# vlc_ctrl.net
KiCad netlist of a schematic drawn in Altium Designer
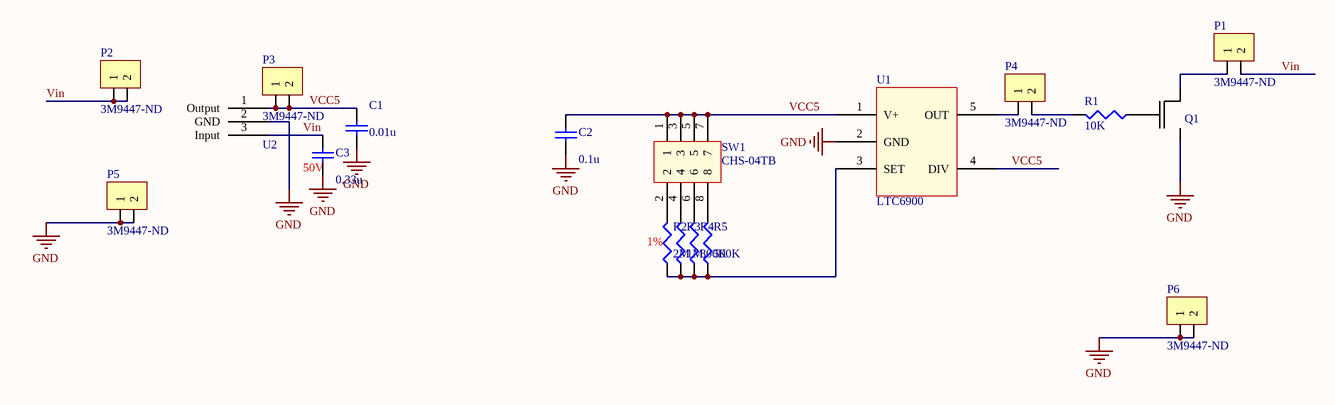
[diagram p0: vlc_ctrl.SchDoc]

(export (version "E")
  (design (tool "Eeschema 10.0.6"))
  (components
    (comp (ref "C1")
      (value "0.01u")
      (footprint "1608[0603]")
      (description "Capacitor (Semiconductor SIM Model)")
      (fields (field (name "Comment") "Cap Semi") (field (name "PUBLISHER") "Altium Limited"))
      (libsource (lib "Miscellaneous Devices") (part "Cap Semi"))
    )
    (comp (ref "C2")
      (value "0.1u")
      (footprint "1608[0603]")
      (description "Capacitor (Semiconductor SIM Model)")
      (fields (field (name "Comment") "Cap Semi") (field (name "PUBLISHER") "Altium Limited"))
      (libsource (lib "Miscellaneous Devices") (part "Cap Semi"))
    )
    (comp (ref "C3")
      (value "0.33u")
      (footprint "1608[0603]")
      (description "Capacitor (Semiconductor SIM Model)")
      (fields (field (name "Comment") "Cap Semi") (field (name "PUBLISHER") "Altium Limited"))
      (libsource (lib "Miscellaneous Devices") (part "Cap Semi"))
    )
    (comp (ref "P1")
      (value "1 x 2 header")
      (footprint "1x2 header")
      (description "100 mils standard header")
      (fields (field (name "SUPPLIER PART NUMBER 1") "3M9447-ND"))
      (libsource (lib "vlc_ctrl") (part "1 x 2 header"))
    )
    (comp (ref "P2")
      (value "1 x 2 header")
      (footprint "1x2 header")
      (description "100 mils standard header")
      (fields (field (name "SUPPLIER PART NUMBER 1") "3M9447-ND"))
      (libsource (lib "vlc_ctrl") (part "1 x 2 header"))
    )
    (comp (ref "P3")
      (value "1 x 2 header")
      (footprint "1x2 header")
      (description "100 mils standard header")
      (fields (field (name "SUPPLIER PART NUMBER 1") "3M9447-ND"))
      (libsource (lib "vlc_ctrl") (part "1 x 2 header"))
    )
    (comp (ref "P4")
      (value "1 x 2 header")
      (footprint "1x2 header")
      (description "100 mils standard header")
      (fields (field (name "SUPPLIER PART NUMBER 1") "3M9447-ND"))
      (libsource (lib "vlc_ctrl") (part "1 x 2 header"))
    )
    (comp (ref "P5")
      (value "1 x 2 header")
      (footprint "1x2 header")
      (description "100 mils standard header")
      (fields (field (name "SUPPLIER PART NUMBER 1") "3M9447-ND"))
      (libsource (lib "vlc_ctrl") (part "1 x 2 header"))
    )
    (comp (ref "P6")
      (value "1 x 2 header")
      (footprint "1x2 header")
      (description "100 mils standard header")
      (fields (field (name "SUPPLIER PART NUMBER 1") "3M9447-ND"))
      (libsource (lib "vlc_ctrl") (part "1 x 2 header"))
    )
    (comp (ref "Q1")
      (value "Si2312CDS")
      (footprint "SOT95P250-3N")
      (description "N-Channel 20 V (D-S) MOSFET")
      (libsource (lib "vlc_ctrl") (part "Si2312CDS"))
    )
    (comp (ref "R1")
      (value "10K")
      (footprint "J1-0603")
      (description "Resistor")
      (fields (field (name "Comment") "Res3") (field (name "PUBLISHER") "Altium Limited"))
      (libsource (lib "Miscellaneous Devices") (part "Res3"))
    )
    (comp (ref "R2")
      (value "2M")
      (footprint "J1-0603")
      (description "Resistor")
      (fields (field (name "Comment") "Res3") (field (name "PUBLISHER") "Altium Limited"))
      (libsource (lib "Miscellaneous Devices") (part "Res3"))
    )
    (comp (ref "R3")
      (value "1M")
      (footprint "J1-0603")
      (description "Resistor")
      (fields (field (name "Comment") "Res3") (field (name "PUBLISHER") "Altium Limited"))
      (libsource (lib "Miscellaneous Devices") (part "Res3"))
    )
    (comp (ref "R4")
      (value "800K")
      (footprint "J1-0603")
      (description "Resistor")
      (fields (field (name "Comment") "Res3") (field (name "PUBLISHER") "Altium Limited"))
      (libsource (lib "Miscellaneous Devices") (part "Res3"))
    )
    (comp (ref "R5")
      (value "500K")
      (footprint "J1-0603")
      (description "Resistor")
      (fields (field (name "Comment") "Res3") (field (name "PUBLISHER") "Altium Limited"))
      (libsource (lib "Miscellaneous Devices") (part "Res3"))
    )
    (comp (ref "SW1")
      (value "CHS-04TB")
      (footprint "CHS04TB")
      (description "SLIDE SWITCHES")
      (libsource (lib "vlc_ctrl") (part "CHS-04TB"))
    )
    (comp (ref "U1")
      (value "LTC6900")
      (footprint "TSOT23")
      (description "Low Power, 1kHz to 20MHz   Resistor Set SOT-23 Oscillator")
      (libsource (lib "vlc_ctrl") (part "LTC6900"))
    )
    (comp (ref "U2")
      (value "LM78L05")
      (footprint "TO92")
      (description "LM78LXX Series 3-Terminal Positive Regulators")
      (libsource (lib "vlc_ctrl") (part "LM78L05"))
    )
  )
  (nets
    (net (code "1") (name "/VCC5") (class "Default")
      (node (ref "C1") (pin "2") (pinfunction "2_2") (pintype "passive"))
      (node (ref "C2") (pin "2") (pinfunction "2_2") (pintype "passive"))
      (node (ref "P3") (pin "1") (pinfunction "1_1") (pintype "passive"))
      (node (ref "P3") (pin "2") (pinfunction "2_2") (pintype "passive"))
      (node (ref "SW1") (pin "1") (pinfunction "1_1") (pintype "passive"))
      (node (ref "SW1") (pin "3") (pinfunction "3_3") (pintype "passive"))
      (node (ref "SW1") (pin "5") (pinfunction "5_5") (pintype "passive"))
      (node (ref "SW1") (pin "7") (pinfunction "7_7") (pintype "passive"))
      (node (ref "U1") (pin "1") (pinfunction "V+_1") (pintype "passive"))
      (node (ref "U1") (pin "4") (pinfunction "DIV_4") (pintype "passive"))
      (node (ref "U2") (pin "1") (pinfunction "Output_1") (pintype "passive"))
    )
    (net (code "2") (name "/Vin") (class "Default")
      (node (ref "C3") (pin "2") (pinfunction "2_2") (pintype "passive"))
      (node (ref "P1") (pin "2") (pinfunction "2_2") (pintype "passive"))
      (node (ref "P2") (pin "1") (pinfunction "1_1") (pintype "passive"))
      (node (ref "P2") (pin "2") (pinfunction "2_2") (pintype "passive"))
      (node (ref "U2") (pin "3") (pinfunction "Input_3") (pintype "passive"))
    )
    (net (code "3") (name "GND") (class "Default")
      (node (ref "C1") (pin "1") (pinfunction "1_1") (pintype "passive"))
      (node (ref "C2") (pin "1") (pinfunction "1_1") (pintype "passive"))
      (node (ref "C3") (pin "1") (pinfunction "1_1") (pintype "passive"))
      (node (ref "P5") (pin "1") (pinfunction "1_1") (pintype "passive"))
      (node (ref "P5") (pin "2") (pinfunction "2_2") (pintype "passive"))
      (node (ref "P6") (pin "1") (pinfunction "1_1") (pintype "passive"))
      (node (ref "P6") (pin "2") (pinfunction "2_2") (pintype "passive"))
      (node (ref "Q1") (pin "2") (pinfunction "S_2") (pintype "passive"))
      (node (ref "U1") (pin "2") (pinfunction "GND_2") (pintype "passive"))
      (node (ref "U2") (pin "2") (pinfunction "GND_2") (pintype "passive"))
    )
    (net (code "4") (name "Net-(P4-Pad2)") (class "Default")
      (node (ref "P4") (pin "2") (pinfunction "2_2") (pintype "passive"))
      (node (ref "R1") (pin "2") (pinfunction "2_2") (pintype "passive"))
    )
    (net (code "5") (name "Net-(Q1-D)") (class "Default")
      (node (ref "P1") (pin "1") (pinfunction "1_1") (pintype "passive"))
      (node (ref "Q1") (pin "3") (pinfunction "D_3") (pintype "passive"))
    )
    (net (code "6") (name "Net-(Q1-G)") (class "Default")
      (node (ref "Q1") (pin "1") (pinfunction "G_1") (pintype "passive"))
      (node (ref "R1") (pin "1") (pinfunction "1_1") (pintype "passive"))
    )
    (net (code "7") (name "Net-(R2-Pad2)") (class "Default")
      (node (ref "R2") (pin "2") (pinfunction "2_2") (pintype "passive"))
      (node (ref "SW1") (pin "2") (pinfunction "2_2") (pintype "passive"))
    )
    (net (code "8") (name "Net-(R3-Pad2)") (class "Default")
      (node (ref "R3") (pin "2") (pinfunction "2_2") (pintype "passive"))
      (node (ref "SW1") (pin "4") (pinfunction "4_4") (pintype "passive"))
    )
    (net (code "9") (name "Net-(R4-Pad2)") (class "Default")
      (node (ref "R4") (pin "2") (pinfunction "2_2") (pintype "passive"))
      (node (ref "SW1") (pin "6") (pinfunction "6_6") (pintype "passive"))
    )
    (net (code "10") (name "Net-(R5-Pad2)") (class "Default")
      (node (ref "R5") (pin "2") (pinfunction "2_2") (pintype "passive"))
      (node (ref "SW1") (pin "8") (pinfunction "8_8") (pintype "passive"))
    )
    (net (code "11") (name "Net-(U1-OUT)") (class "Default")
      (node (ref "P4") (pin "1") (pinfunction "1_1") (pintype "passive"))
      (node (ref "U1") (pin "5") (pinfunction "OUT_5") (pintype "passive"))
    )
    (net (code "12") (name "Net-(U1-SET)") (class "Default")
      (node (ref "R2") (pin "1") (pinfunction "1_1") (pintype "passive"))
      (node (ref "R3") (pin "1") (pinfunction "1_1") (pintype "passive"))
      (node (ref "R4") (pin "1") (pinfunction "1_1") (pintype "passive"))
      (node (ref "R5") (pin "1") (pinfunction "1_1") (pintype "passive"))
      (node (ref "U1") (pin "3") (pinfunction "SET_3") (pintype "passive"))
    )
  )
)
